# SCH_pls-work-pls-work-pls-work-pls-work_.net
KiCad netlist of a schematic drawn in EasyEDA
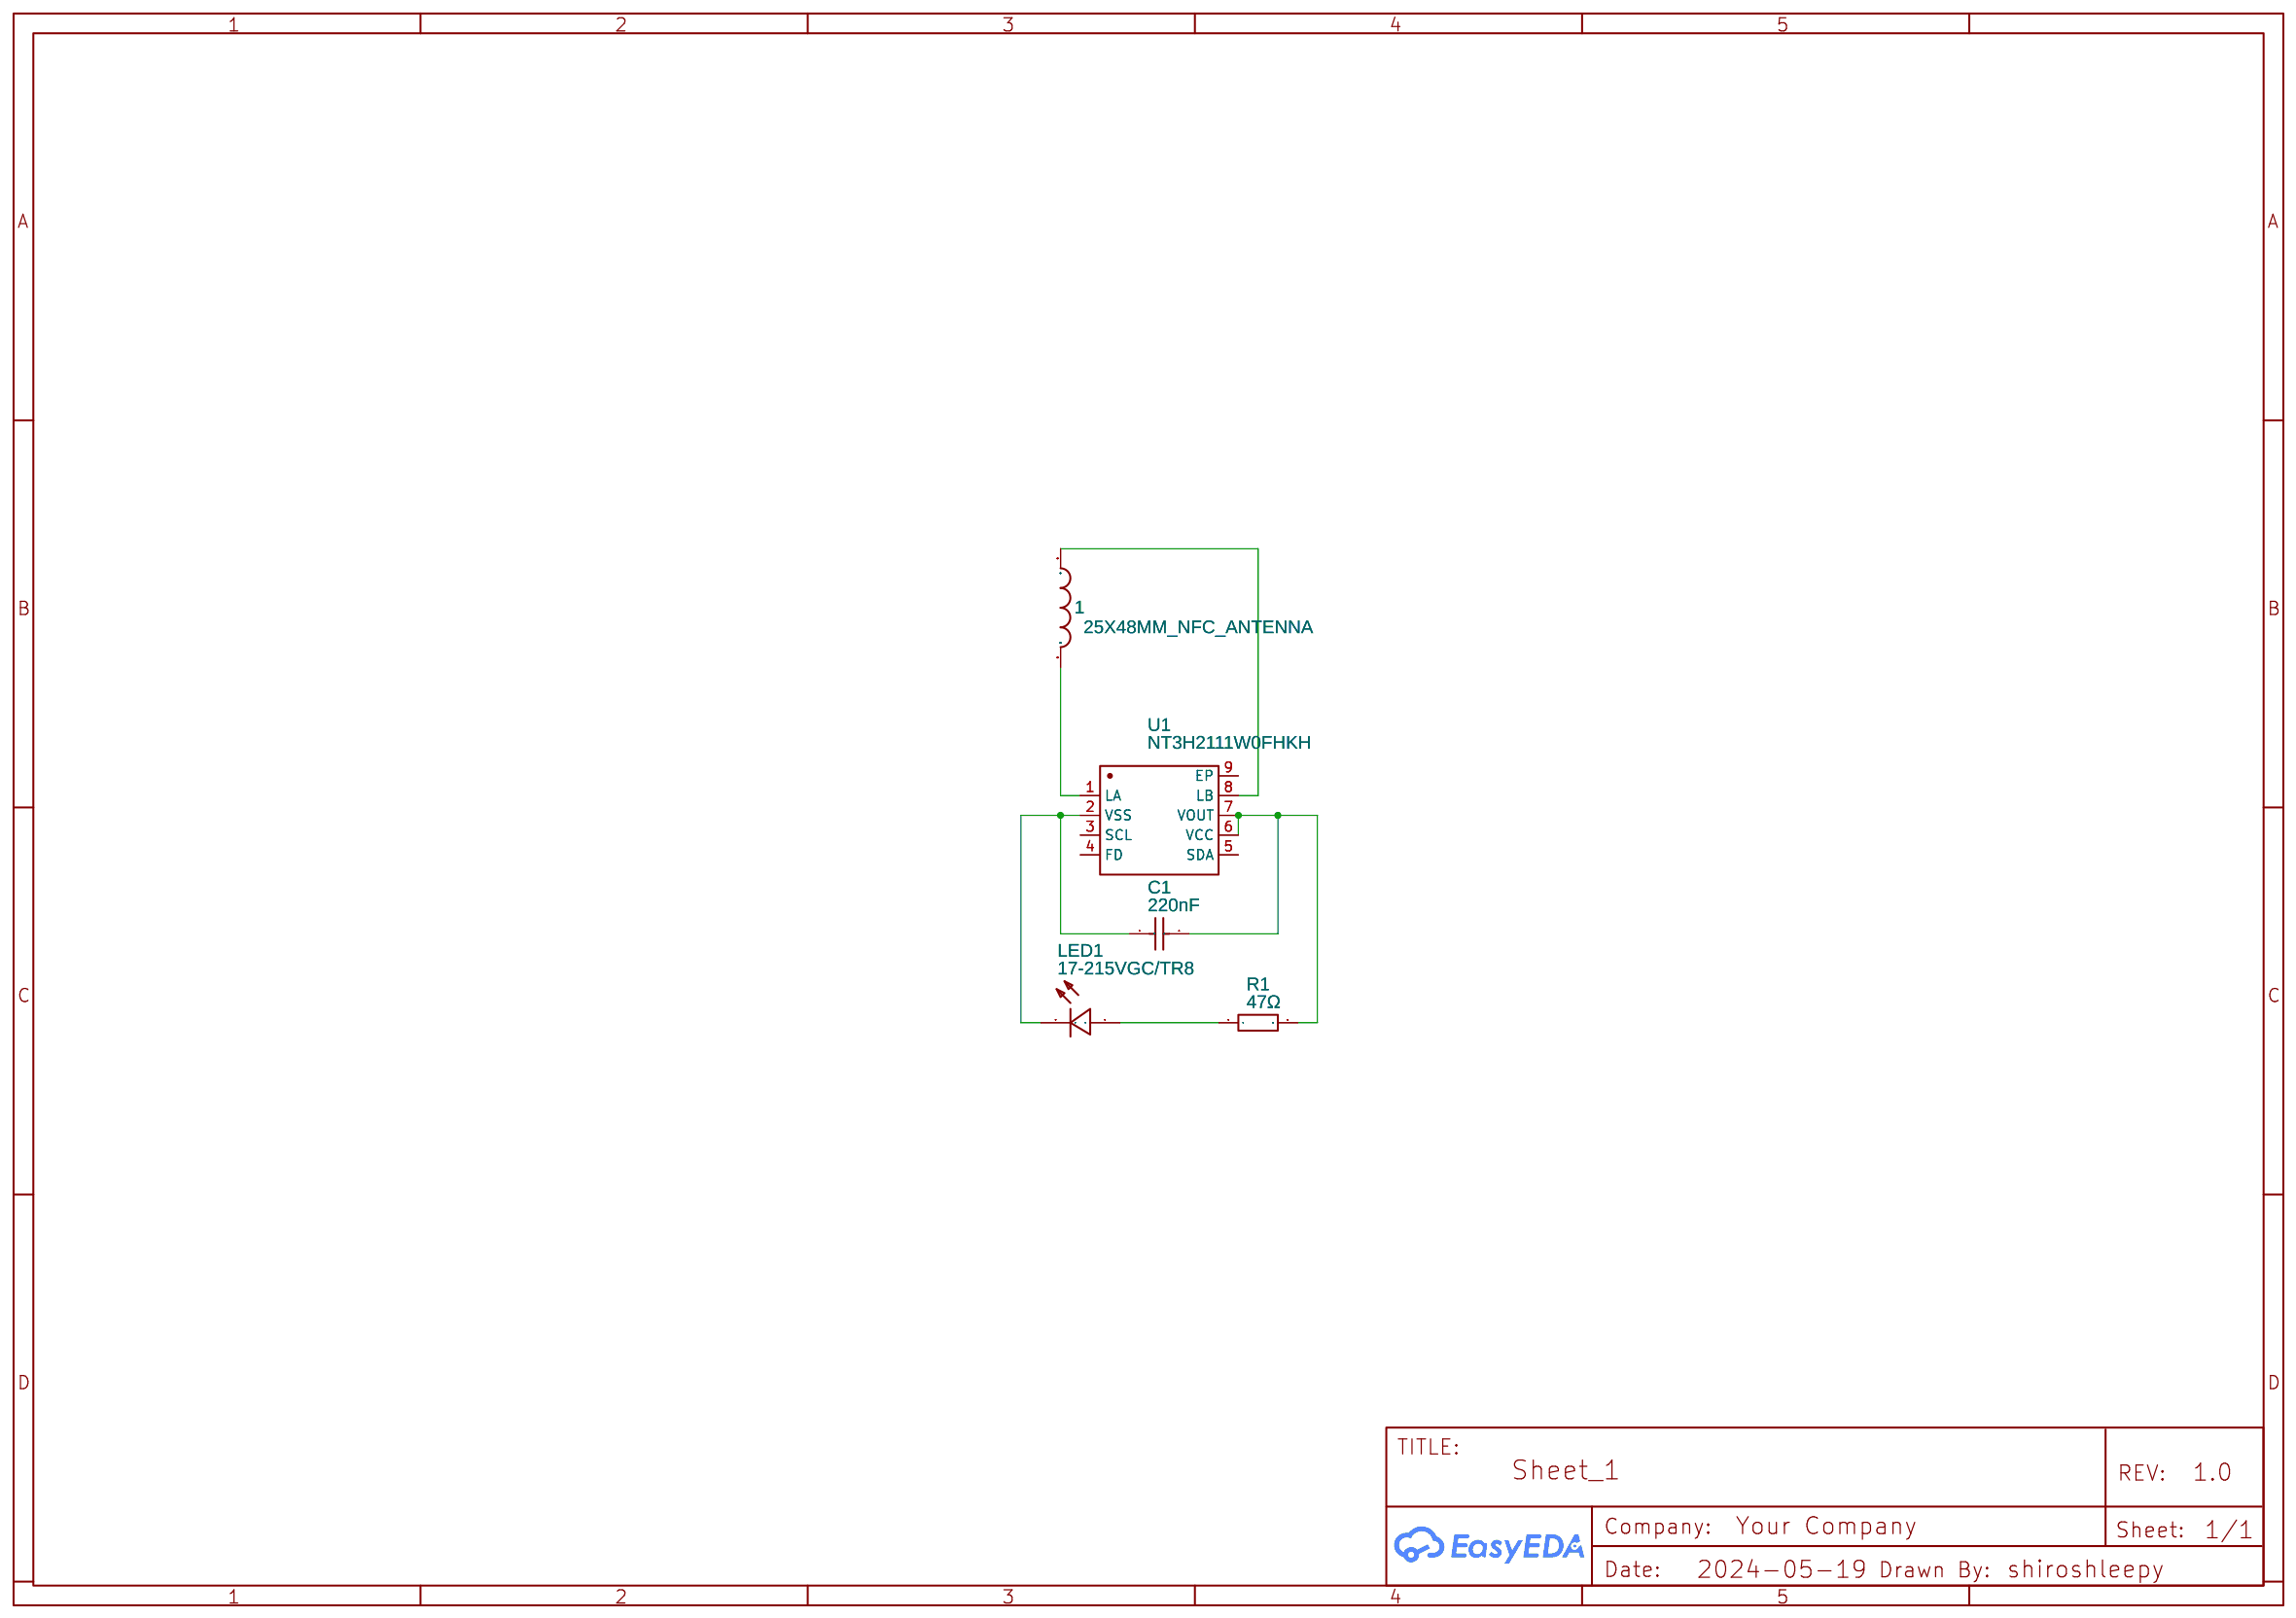
[diagram p0: schematic sheet]

(export (version "E")
  (design (tool "Eeschema 10.0.6"))
  (components
    (comp (ref "1") (value "25X48MM_NFC_ANTENNA") (libsource (lib "") (part "25X48MM_NFC_ANTENNA")))
    (comp (ref "C1")
      (value "220nF")
      (fields
        (field (name "Manufacturer Part") "CL10B224KA8NNNC")
        (field (name "Manufacturer") "SAMSUNG(三星)")
      )
      (libsource (lib "") (part "CL10B224KA8NNNC"))
    )
    (comp (ref "LED1")
      (value "17-215VGC/TR8")
      (fields (field (name "Manufacturer") "EVERLIGHT(亿光)"))
      (libsource (lib "") (part "17-215VGC/TR8"))
    )
    (comp (ref "R1")
      (value "47Ω")
      (fields
        (field (name "Manufacturer Part") "0603WAF470JT5E")
        (field (name "Manufacturer") "UNI-ROYAL(厚声)")
      )
      (libsource (lib "") (part "0603WAF470JT5E"))
    )
    (comp (ref "U1")
      (value "NT3H2111W0FHKH")
      (fields (field (name "Manufacturer") "NXP(恩智浦)"))
      (libsource (lib "") (part "NT3H2111W0FHKH"))
    )
  )
  (nets
    (net (code "1") (name "Net-(LED1-A)") (class "Default")
      (node (ref "LED1") (pin "1") (pinfunction "A_1") (pintype "unspecified"))
      (node (ref "R1") (pin "1") (pinfunction "1_1") (pintype "input"))
    )
    (net (code "2") (name "Net-(LED1-K)") (class "Default")
      (node (ref "C1") (pin "1") (pinfunction "1_1") (pintype "input"))
      (node (ref "LED1") (pin "2") (pinfunction "K_2") (pintype "unspecified"))
      (node (ref "U1") (pin "2") (pinfunction "VSS_2") (pintype "unspecified"))
    )
    (net (code "3") (name "Net-(U1-LA)") (class "Default")
      (node (ref "1") (pin "P$2") (pinfunction "P$2_P$2") (pintype "bidirectional"))
      (node (ref "U1") (pin "1") (pinfunction "LA_1") (pintype "unspecified"))
    )
    (net (code "4") (name "Net-(U1-LB)") (class "Default")
      (node (ref "1") (pin "P$1") (pinfunction "P$1_P$1") (pintype "bidirectional"))
      (node (ref "U1") (pin "8") (pinfunction "LB_8") (pintype "unspecified"))
    )
    (net (code "5") (name "Net-(U1-VCC)") (class "Default")
      (node (ref "C1") (pin "2") (pinfunction "2_2") (pintype "input"))
      (node (ref "R1") (pin "2") (pinfunction "2_2") (pintype "input"))
      (node (ref "U1") (pin "6") (pinfunction "VCC_6") (pintype "unspecified"))
      (node (ref "U1") (pin "7") (pinfunction "VOUT_7") (pintype "unspecified"))
    )
    (net (code "6") (name "unconnected-(U1-EP-Pad9)") (class "Default")
      (node (ref "U1") (pin "9") (pinfunction "EP_9") (pintype "unspecified"))
    )
    (net (code "7") (name "unconnected-(U1-FD-Pad4)") (class "Default")
      (node (ref "U1") (pin "4") (pinfunction "FD_4") (pintype "unspecified"))
    )
    (net (code "8") (name "unconnected-(U1-SCL-Pad3)") (class "Default")
      (node (ref "U1") (pin "3") (pinfunction "SCL_3") (pintype "unspecified"))
    )
    (net (code "9") (name "unconnected-(U1-SDA-Pad5)") (class "Default")
      (node (ref "U1") (pin "5") (pinfunction "SDA_5") (pintype "unspecified"))
    )
  )
)
